# L298N.net
KiCad netlist of a schematic drawn in Altium Designer
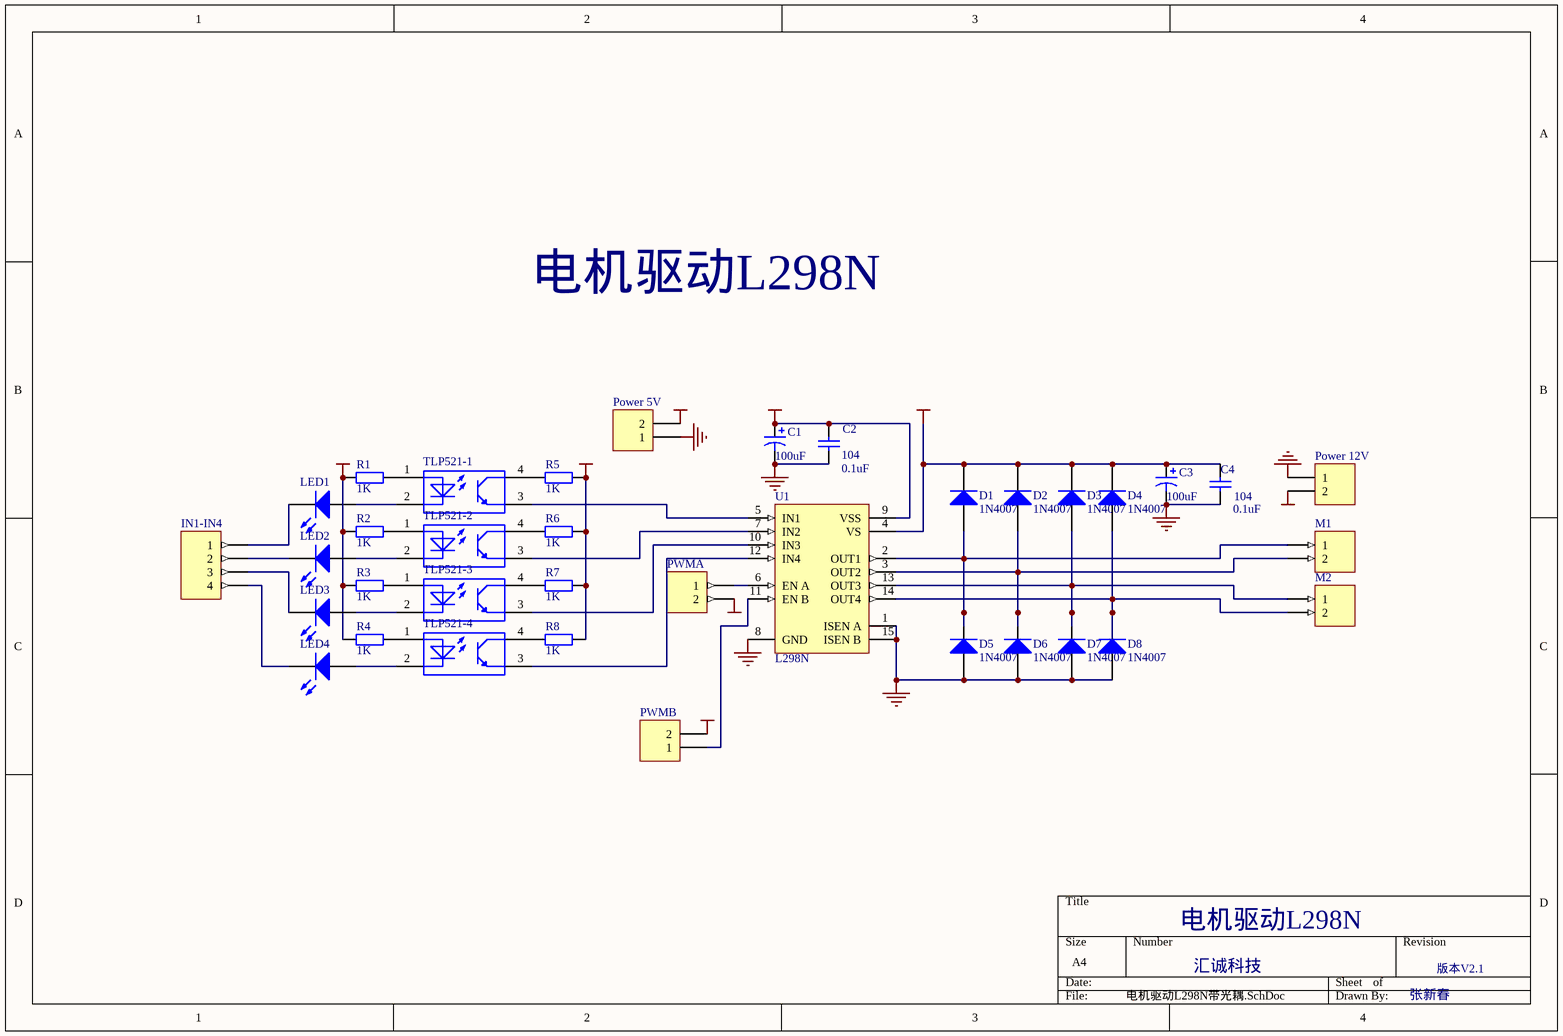
[diagram p0: 电机驱动L298N带光耦.SchDoc]

(export (version "E")
  (design (tool "Eeschema 10.0.6"))
  (components
    (comp (ref "C1")
      (value "100uF")
      (footprint "CAPPR2-5x6.8")
      (description "Polarized Capacitor (Surface Mount)")
      (fields (field (name "PUBLISHER") "Altium Limited"))
      (libsource (lib "Miscellaneous Devices") (part "Cap Pol3"))
    )
    (comp (ref "C2")
      (value "104")
      (footprint "BAT-2")
      (description "Capacitor")
      (fields (field (name "ALTIUM_VALUE") "0.1uF") (field (name "PUBLISHER") "Altium Limited"))
      (libsource (lib "Miscellaneous Devices") (part "Cap"))
    )
    (comp (ref "C3")
      (value "100uF")
      (footprint "CAPPR2-5x6.8")
      (description "Polarized Capacitor (Surface Mount)")
      (fields (field (name "PUBLISHER") "Altium Limited"))
      (libsource (lib "Miscellaneous Devices") (part "Cap Pol3"))
    )
    (comp (ref "C4")
      (value "104")
      (footprint "BAT-2")
      (description "Capacitor")
      (fields (field (name "ALTIUM_VALUE") "0.1uF") (field (name "PUBLISHER") "Altium Limited"))
      (libsource (lib "Miscellaneous Devices") (part "Cap"))
    )
    (comp (ref "D1")
      (value "1N4007")
      (footprint "DIO10.46-5.3x2.8")
      (description "1 Amp General Purpose Rectifier")
      (fields (field (name "PUBLISHER") "Altium Limited"))
      (libsource (lib "Miscellaneous Devices") (part "Diode 1N4007"))
    )
    (comp (ref "D2")
      (value "1N4007")
      (footprint "DIO10.46-5.3x2.8")
      (description "1 Amp General Purpose Rectifier")
      (fields (field (name "PUBLISHER") "Altium Limited"))
      (libsource (lib "Miscellaneous Devices") (part "Diode 1N4007"))
    )
    (comp (ref "D3")
      (value "1N4007")
      (footprint "DIO10.46-5.3x2.8")
      (description "1 Amp General Purpose Rectifier")
      (fields (field (name "PUBLISHER") "Altium Limited"))
      (libsource (lib "Miscellaneous Devices") (part "Diode 1N4007"))
    )
    (comp (ref "D4")
      (value "1N4007")
      (footprint "DIO10.46-5.3x2.8")
      (description "1 Amp General Purpose Rectifier")
      (fields (field (name "PUBLISHER") "Altium Limited"))
      (libsource (lib "Miscellaneous Devices") (part "Diode 1N4007"))
    )
    (comp (ref "D5")
      (value "1N4007")
      (footprint "DIO10.46-5.3x2.8")
      (description "1 Amp General Purpose Rectifier")
      (fields (field (name "PUBLISHER") "Altium Limited"))
      (libsource (lib "Miscellaneous Devices") (part "Diode 1N4007"))
    )
    (comp (ref "D6")
      (value "1N4007")
      (footprint "DIO10.46-5.3x2.8")
      (description "1 Amp General Purpose Rectifier")
      (fields (field (name "PUBLISHER") "Altium Limited"))
      (libsource (lib "Miscellaneous Devices") (part "Diode 1N4007"))
    )
    (comp (ref "D7")
      (value "1N4007")
      (footprint "DIO10.46-5.3x2.8")
      (description "1 Amp General Purpose Rectifier")
      (fields (field (name "PUBLISHER") "Altium Limited"))
      (libsource (lib "Miscellaneous Devices") (part "Diode 1N4007"))
    )
    (comp (ref "D8")
      (value "1N4007")
      (footprint "DIO10.46-5.3x2.8")
      (description "1 Amp General Purpose Rectifier")
      (fields (field (name "PUBLISHER") "Altium Limited"))
      (libsource (lib "Miscellaneous Devices") (part "Diode 1N4007"))
    )
    (comp (ref "IN1-IN4")
      (value "~")
      (footprint "HDR1X4")
      (description "Header, 4-Pin")
      (fields (field (name "PUBLISHER") "Altium Limited"))
      (libsource (lib "Miscellaneous Connectors") (part "MHDR1X4"))
    )
    (comp (ref "LED1")
      (value "~")
      (footprint "HDR1X2")
      (description "Typical BLUE SiC LED")
      (fields (field (name "PUBLISHER") "Altium Limited"))
      (libsource (lib "Miscellaneous Devices") (part "LED3"))
    )
    (comp (ref "LED2")
      (value "~")
      (footprint "HDR1X2")
      (description "Typical BLUE SiC LED")
      (fields (field (name "PUBLISHER") "Altium Limited"))
      (libsource (lib "Miscellaneous Devices") (part "LED3"))
    )
    (comp (ref "LED3")
      (value "~")
      (footprint "HDR1X2")
      (description "Typical BLUE SiC LED")
      (fields (field (name "PUBLISHER") "Altium Limited"))
      (libsource (lib "Miscellaneous Devices") (part "LED3"))
    )
    (comp (ref "LED4")
      (value "~")
      (footprint "HDR1X2")
      (description "Typical BLUE SiC LED")
      (fields (field (name "PUBLISHER") "Altium Limited"))
      (libsource (lib "Miscellaneous Devices") (part "LED3"))
    )
    (comp (ref "M1")
      (value "~")
      (footprint "PCBComponent_1")
      (description "Header, 2-Pin")
      (fields (field (name "PUBLISHER") "Altium Limited"))
      (libsource (lib "") (part "MHDR1X2_2"))
    )
    (comp (ref "M2")
      (value "~")
      (footprint "PCBComponent_1")
      (description "Header, 2-Pin")
      (fields (field (name "PUBLISHER") "Altium Limited"))
      (libsource (lib "") (part "MHDR1X2_2"))
    )
    (comp (ref "Power 5V")
      (value "~")
      (footprint "HDR1X2")
      (description "Header, 2-Pin")
      (fields (field (name "PUBLISHER") "Altium Limited"))
      (libsource (lib "Miscellaneous Connectors") (part "MHDR1X2"))
    )
    (comp (ref "Power 12V")
      (value "~")
      (footprint "PCBComponent_1")
      (description "Header, 2-Pin")
      (fields (field (name "PUBLISHER") "Altium Limited"))
      (libsource (lib "") (part "MHDR1X2_1"))
    )
    (comp (ref "PWMA")
      (value "~")
      (footprint "HDR1X2")
      (description "Header, 2-Pin")
      (fields (field (name "PUBLISHER") "Altium Limited"))
      (libsource (lib "") (part "MHDR1X2_3"))
    )
    (comp (ref "PWMB")
      (value "~")
      (footprint "HDR1X2")
      (description "Header, 2-Pin")
      (fields (field (name "PUBLISHER") "Altium Limited"))
      (libsource (lib "Miscellaneous Connectors") (part "MHDR1X2"))
    )
    (comp (ref "R1")
      (value "1K")
      (footprint "HDR1X2")
      (description "Resistor")
      (fields (field (name "PUBLISHER") "Altium Limited"))
      (libsource (lib "Miscellaneous Devices") (part "Res2"))
    )
    (comp (ref "R2")
      (value "1K")
      (footprint "HDR1X2")
      (description "Resistor")
      (fields (field (name "PUBLISHER") "Altium Limited"))
      (libsource (lib "Miscellaneous Devices") (part "Res2"))
    )
    (comp (ref "R3")
      (value "1K")
      (footprint "HDR1X2")
      (description "Resistor")
      (fields (field (name "PUBLISHER") "Altium Limited"))
      (libsource (lib "Miscellaneous Devices") (part "Res2"))
    )
    (comp (ref "R4")
      (value "1K")
      (footprint "HDR1X2")
      (description "Resistor")
      (fields (field (name "PUBLISHER") "Altium Limited"))
      (libsource (lib "Miscellaneous Devices") (part "Res2"))
    )
    (comp (ref "R5")
      (value "1K")
      (footprint "HDR1X2")
      (description "Resistor")
      (fields (field (name "PUBLISHER") "Altium Limited"))
      (libsource (lib "Miscellaneous Devices") (part "Res2"))
    )
    (comp (ref "R6")
      (value "1K")
      (footprint "HDR1X2")
      (description "Resistor")
      (fields (field (name "PUBLISHER") "Altium Limited"))
      (libsource (lib "Miscellaneous Devices") (part "Res2"))
    )
    (comp (ref "R7")
      (value "1K")
      (footprint "HDR1X2")
      (description "Resistor")
      (fields (field (name "PUBLISHER") "Altium Limited"))
      (libsource (lib "Miscellaneous Devices") (part "Res2"))
    )
    (comp (ref "R8")
      (value "1K")
      (footprint "HDR1X2")
      (description "Resistor")
      (fields (field (name "PUBLISHER") "Altium Limited"))
      (libsource (lib "Miscellaneous Devices") (part "Res2"))
    )
    (comp (ref "TLP521-1") (value "~") (footprint "DIP4") (libsource (lib "MyInt_Lib") (part "TLP521-1")))
    (comp (ref "TLP521-2") (value "~") (footprint "DIP4") (libsource (lib "MyInt_Lib") (part "TLP521-1")))
    (comp (ref "TLP521-3") (value "~") (footprint "DIP4") (libsource (lib "MyInt_Lib") (part "TLP521-1")))
    (comp (ref "TLP521-4") (value "~") (footprint "DIP4") (libsource (lib "MyInt_Lib") (part "TLP521-1")))
    (comp (ref "U1")
      (value "L298N")
      (footprint "DFM-T15/X1.6V")
      (description "Dual Full Bridge Driver")
      (fields (field (name "PUBLISHER") "Altium Limited"))
      (libsource (lib "ST Interface DC Motor Controller") (part "L298N"))
    )
  )
  (nets
    (net (code "1") (name "+5V") (class "Default")
      (node (ref "C1") (pin "1") (pinfunction "1_1") (pintype "passive"))
      (node (ref "C2") (pin "2") (pinfunction "2_2") (pintype "passive"))
      (node (ref "PWMA") (pin "2") (pinfunction "2_2") (pintype "output"))
      (node (ref "PWMB") (pin "2") (pinfunction "2_2") (pintype "power_in"))
      (node (ref "Power 5V") (pin "2") (pinfunction "2_2") (pintype "power_in"))
      (node (ref "R1") (pin "1") (pinfunction "1_1") (pintype "passive"))
      (node (ref "R2") (pin "1") (pinfunction "1_1") (pintype "passive"))
      (node (ref "R3") (pin "1") (pinfunction "1_1") (pintype "passive"))
      (node (ref "R4") (pin "1") (pinfunction "1_1") (pintype "passive"))
      (node (ref "R5") (pin "2") (pinfunction "2_2") (pintype "passive"))
      (node (ref "R6") (pin "2") (pinfunction "2_2") (pintype "passive"))
      (node (ref "R7") (pin "2") (pinfunction "2_2") (pintype "passive"))
      (node (ref "R8") (pin "2") (pinfunction "2_2") (pintype "passive"))
      (node (ref "U1") (pin "9") (pinfunction "VSS_9") (pintype "power_in"))
    )
    (net (code "2") (name "+12V") (class "Default")
      (node (ref "C3") (pin "1") (pinfunction "1_1") (pintype "passive"))
      (node (ref "C4") (pin "2") (pinfunction "2_2") (pintype "passive"))
      (node (ref "D1") (pin "2") (pinfunction "K_2") (pintype "passive"))
      (node (ref "D2") (pin "2") (pinfunction "K_2") (pintype "passive"))
      (node (ref "D3") (pin "2") (pinfunction "K_2") (pintype "passive"))
      (node (ref "D4") (pin "2") (pinfunction "K_2") (pintype "passive"))
      (node (ref "Power 12V") (pin "2") (pinfunction "2_2") (pintype "power_in"))
      (node (ref "U1") (pin "4") (pinfunction "VS_4") (pintype "power_in"))
    )
    (net (code "3") (name "GND") (class "Default")
      (node (ref "C1") (pin "2") (pinfunction "2_2") (pintype "passive"))
      (node (ref "C2") (pin "1") (pinfunction "1_1") (pintype "passive"))
      (node (ref "C3") (pin "2") (pinfunction "2_2") (pintype "passive"))
      (node (ref "C4") (pin "1") (pinfunction "1_1") (pintype "passive"))
      (node (ref "D5") (pin "1") (pinfunction "A_1") (pintype "passive"))
      (node (ref "D6") (pin "1") (pinfunction "A_1") (pintype "passive"))
      (node (ref "D7") (pin "1") (pinfunction "A_1") (pintype "passive"))
      (node (ref "D8") (pin "1") (pinfunction "A_1") (pintype "passive"))
      (node (ref "Power 12V") (pin "1") (pinfunction "1_1") (pintype "power_in"))
      (node (ref "Power 5V") (pin "1") (pinfunction "1_1") (pintype "power_in"))
      (node (ref "U1") (pin "1") (pinfunction "ISEN_A_1") (pintype "passive"))
      (node (ref "U1") (pin "15") (pinfunction "ISEN_B_15") (pintype "passive"))
      (node (ref "U1") (pin "8") (pinfunction "GND_8") (pintype "power_in"))
    )
    (net (code "4") (name "Net-(D1-A)") (class "Default")
      (node (ref "D1") (pin "1") (pinfunction "A_1") (pintype "passive"))
      (node (ref "D5") (pin "2") (pinfunction "K_2") (pintype "passive"))
      (node (ref "M1") (pin "1") (pinfunction "1_1") (pintype "input"))
      (node (ref "U1") (pin "2") (pinfunction "OUT1_2") (pintype "output"))
    )
    (net (code "5") (name "Net-(D2-A)") (class "Default")
      (node (ref "D2") (pin "1") (pinfunction "A_1") (pintype "passive"))
      (node (ref "D6") (pin "2") (pinfunction "K_2") (pintype "passive"))
      (node (ref "M1") (pin "2") (pinfunction "2_2") (pintype "input"))
      (node (ref "U1") (pin "3") (pinfunction "OUT2_3") (pintype "output"))
    )
    (net (code "6") (name "Net-(D3-A)") (class "Default")
      (node (ref "D3") (pin "1") (pinfunction "A_1") (pintype "passive"))
      (node (ref "D7") (pin "2") (pinfunction "K_2") (pintype "passive"))
      (node (ref "M2") (pin "1") (pinfunction "1_1") (pintype "input"))
      (node (ref "U1") (pin "13") (pinfunction "OUT3_13") (pintype "output"))
    )
    (net (code "7") (name "Net-(D4-A)") (class "Default")
      (node (ref "D4") (pin "1") (pinfunction "A_1") (pintype "passive"))
      (node (ref "D8") (pin "2") (pinfunction "K_2") (pintype "passive"))
      (node (ref "M2") (pin "2") (pinfunction "2_2") (pintype "input"))
      (node (ref "U1") (pin "14") (pinfunction "OUT4_14") (pintype "output"))
    )
    (net (code "8") (name "Net-(LED1-A)") (class "Default")
      (node (ref "LED1") (pin "1") (pinfunction "A_1") (pintype "passive"))
      (node (ref "TLP521-1") (pin "2") (pinfunction "2_2") (pintype "passive"))
    )
    (net (code "9") (name "Net-(LED1-K)") (class "Default")
      (node (ref "IN1-IN4") (pin "1") (pinfunction "1_1") (pintype "output"))
      (node (ref "LED1") (pin "2") (pinfunction "K_2") (pintype "passive"))
    )
    (net (code "10") (name "Net-(LED2-A)") (class "Default")
      (node (ref "LED2") (pin "1") (pinfunction "A_1") (pintype "passive"))
      (node (ref "TLP521-2") (pin "2") (pinfunction "2_2") (pintype "passive"))
    )
    (net (code "11") (name "Net-(LED2-K)") (class "Default")
      (node (ref "IN1-IN4") (pin "2") (pinfunction "2_2") (pintype "output"))
      (node (ref "LED2") (pin "2") (pinfunction "K_2") (pintype "passive"))
    )
    (net (code "12") (name "Net-(LED3-A)") (class "Default")
      (node (ref "LED3") (pin "1") (pinfunction "A_1") (pintype "passive"))
      (node (ref "TLP521-3") (pin "2") (pinfunction "2_2") (pintype "passive"))
    )
    (net (code "13") (name "Net-(LED3-K)") (class "Default")
      (node (ref "IN1-IN4") (pin "3") (pinfunction "3_3") (pintype "output"))
      (node (ref "LED3") (pin "2") (pinfunction "K_2") (pintype "passive"))
    )
    (net (code "14") (name "Net-(LED4-A)") (class "Default")
      (node (ref "LED4") (pin "1") (pinfunction "A_1") (pintype "passive"))
      (node (ref "TLP521-4") (pin "2") (pinfunction "2_2") (pintype "passive"))
    )
    (net (code "15") (name "Net-(LED4-K)") (class "Default")
      (node (ref "IN1-IN4") (pin "4") (pinfunction "4_4") (pintype "output"))
      (node (ref "LED4") (pin "2") (pinfunction "K_2") (pintype "passive"))
    )
    (net (code "16") (name "Net-(R1-Pad2)") (class "Default")
      (node (ref "R1") (pin "2") (pinfunction "2_2") (pintype "passive"))
      (node (ref "TLP521-1") (pin "1") (pinfunction "1_1") (pintype "passive"))
    )
    (net (code "17") (name "Net-(R2-Pad2)") (class "Default")
      (node (ref "R2") (pin "2") (pinfunction "2_2") (pintype "passive"))
      (node (ref "TLP521-2") (pin "1") (pinfunction "1_1") (pintype "passive"))
    )
    (net (code "18") (name "Net-(R3-Pad2)") (class "Default")
      (node (ref "R3") (pin "2") (pinfunction "2_2") (pintype "passive"))
      (node (ref "TLP521-3") (pin "1") (pinfunction "1_1") (pintype "passive"))
    )
    (net (code "19") (name "Net-(R4-Pad2)") (class "Default")
      (node (ref "R4") (pin "2") (pinfunction "2_2") (pintype "passive"))
      (node (ref "TLP521-4") (pin "1") (pinfunction "1_1") (pintype "passive"))
    )
    (net (code "20") (name "Net-(R5-Pad1)") (class "Default")
      (node (ref "R5") (pin "1") (pinfunction "1_1") (pintype "passive"))
      (node (ref "TLP521-1") (pin "4") (pinfunction "4_4") (pintype "passive"))
    )
    (net (code "21") (name "Net-(R6-Pad1)") (class "Default")
      (node (ref "R6") (pin "1") (pinfunction "1_1") (pintype "passive"))
      (node (ref "TLP521-2") (pin "4") (pinfunction "4_4") (pintype "passive"))
    )
    (net (code "22") (name "Net-(R7-Pad1)") (class "Default")
      (node (ref "R7") (pin "1") (pinfunction "1_1") (pintype "passive"))
      (node (ref "TLP521-3") (pin "4") (pinfunction "4_4") (pintype "passive"))
    )
    (net (code "23") (name "Net-(R8-Pad1)") (class "Default")
      (node (ref "R8") (pin "1") (pinfunction "1_1") (pintype "passive"))
      (node (ref "TLP521-4") (pin "4") (pinfunction "4_4") (pintype "passive"))
    )
    (net (code "24") (name "Net-(U1-EN_A)") (class "Default")
      (node (ref "PWMA") (pin "1") (pinfunction "1_1") (pintype "output"))
      (node (ref "U1") (pin "6") (pinfunction "EN_A_6") (pintype "input"))
    )
    (net (code "25") (name "Net-(U1-EN_B)") (class "Default")
      (node (ref "PWMB") (pin "1") (pinfunction "1_1") (pintype "power_in"))
      (node (ref "U1") (pin "11") (pinfunction "EN_B_11") (pintype "input"))
    )
    (net (code "26") (name "Net-(U1-IN1)") (class "Default")
      (node (ref "TLP521-1") (pin "3") (pinfunction "3_3") (pintype "passive"))
      (node (ref "U1") (pin "5") (pinfunction "IN1_5") (pintype "input"))
    )
    (net (code "27") (name "Net-(U1-IN2)") (class "Default")
      (node (ref "TLP521-2") (pin "3") (pinfunction "3_3") (pintype "passive"))
      (node (ref "U1") (pin "7") (pinfunction "IN2_7") (pintype "input"))
    )
    (net (code "28") (name "Net-(U1-IN3)") (class "Default")
      (node (ref "TLP521-3") (pin "3") (pinfunction "3_3") (pintype "passive"))
      (node (ref "U1") (pin "10") (pinfunction "IN3_10") (pintype "input"))
    )
    (net (code "29") (name "Net-(U1-IN4)") (class "Default")
      (node (ref "TLP521-4") (pin "3") (pinfunction "3_3") (pintype "passive"))
      (node (ref "U1") (pin "12") (pinfunction "IN4_12") (pintype "input"))
    )
  )
)
